# firealarm.net
KiCad netlist of a schematic drawn in EAGLE
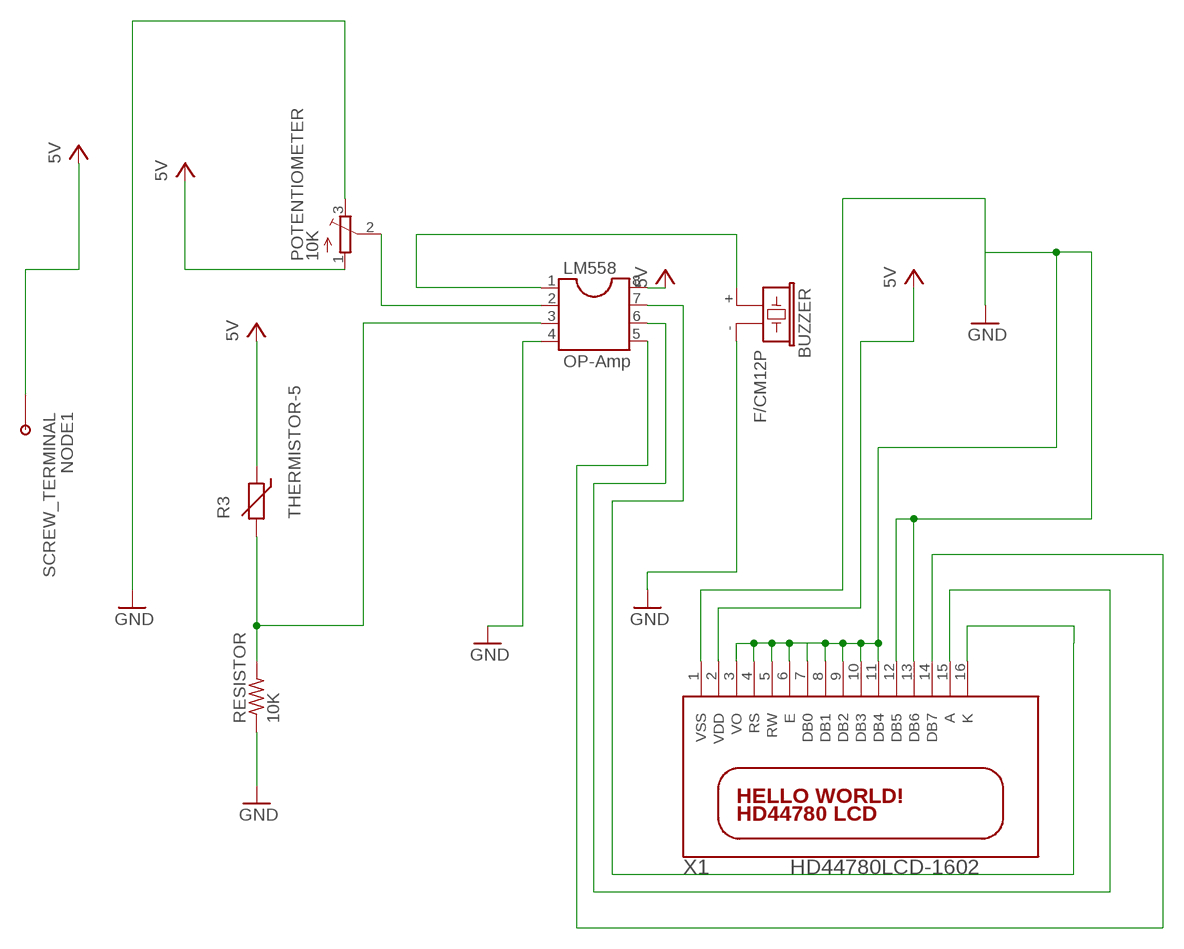
[diagram p0: schematic, sheet 1]

(export (version "E")
  (design (tool "Eeschema 10.0.6"))
  (components
    (comp (ref "BUZZER")
      (value "F/CM12P")
      (footprint "eagle-import:F_CM12P")
      (libsource (lib "eagle-import") (part "F/CM12P"))
    )
    (comp (ref "LM558")
      (value "OP-Amp")
      (footprint "eagle-import:SOCKET-08")
      (libsource (lib "eagle-import") (part "DIL8S"))
    )
    (comp (ref "NODE1")
      (value "SCREW_TERMINAL")
      (footprint "eagle-import:NINIGI_PCB_1M4")
      (libsource (lib "eagle-import") (part "PCB_SCREW_TERMINAL"))
    )
    (comp (ref "POTENTIOMETER")
      (value "10K")
      (footprint "eagle-import:3223G")
      (libsource (lib "eagle-import") (part "TRIM_EU-3223G"))
    )
    (comp (ref "R3")
      (value "THERMISTOR-5")
      (footprint "eagle-import:R-5")
      (libsource (lib "eagle-import") (part "THERMISTOR-5"))
    )
    (comp (ref "RESISTOR")
      (value "10K")
      (footprint "eagle-import:0204V")
      (libsource (lib "eagle-import") (part "R-US_0204/2V"))
    )
    (comp (ref "X1")
      (value "HD44780LCD-1602")
      (footprint "eagle-import:LCD1602")
      (libsource (lib "eagle-import") (part "HD44780LCD-1602"))
    )
  )
  (nets
    (net (code "1") (name "5V") (class "Default")
      (node (ref "LM558") (pin "8") (pinfunction "8_8") (pintype "passive"))
      (node (ref "NODE1") (pin "1") (pinfunction "P$1_1") (pintype "bidirectional"))
      (node (ref "NODE1") (pin "2") (pinfunction "P$1_2") (pintype "bidirectional"))
      (node (ref "NODE1") (pin "3") (pinfunction "P$1_3") (pintype "bidirectional"))
      (node (ref "NODE1") (pin "4") (pinfunction "P$1_4") (pintype "bidirectional"))
      (node (ref "NODE1") (pin "C") (pinfunction "P$1_C") (pintype "bidirectional"))
      (node (ref "POTENTIOMETER") (pin "1") (pinfunction "A_1") (pintype "passive"))
      (node (ref "R3") (pin "1") (pinfunction "1_1") (pintype "passive"))
      (node (ref "X1") (pin "2") (pinfunction "VDD_2") (pintype "power_in"))
    )
    (net (code "2") (name "GND") (class "Default")
      (node (ref "BUZZER") (pin "-") (pinfunction "2_-") (pintype "passive"))
      (node (ref "LM558") (pin "4") (pinfunction "4_4") (pintype "passive"))
      (node (ref "POTENTIOMETER") (pin "3") (pinfunction "E_3") (pintype "passive"))
      (node (ref "RESISTOR") (pin "1") (pinfunction "1_1") (pintype "passive"))
      (node (ref "X1") (pin "1") (pinfunction "VSS_1") (pintype "power_in"))
      (node (ref "X1") (pin "10") (pinfunction "DB3_10") (pintype "bidirectional"))
      (node (ref "X1") (pin "11") (pinfunction "DB4_11") (pintype "bidirectional"))
      (node (ref "X1") (pin "12") (pinfunction "DB5_12") (pintype "bidirectional"))
      (node (ref "X1") (pin "13") (pinfunction "DB6_13") (pintype "bidirectional"))
      (node (ref "X1") (pin "3") (pinfunction "VO_3") (pintype "input"))
      (node (ref "X1") (pin "4") (pinfunction "RS_4") (pintype "input"))
      (node (ref "X1") (pin "5") (pinfunction "RW_5") (pintype "input"))
      (node (ref "X1") (pin "6") (pinfunction "E_6") (pintype "input"))
      (node (ref "X1") (pin "8") (pinfunction "DB1_8") (pintype "bidirectional"))
      (node (ref "X1") (pin "9") (pinfunction "DB2_9") (pintype "bidirectional"))
    )
    (net (code "3") (name "Net-(BUZZER-1)") (class "Default")
      (node (ref "BUZZER") (pin "+") (pinfunction "1_+") (pintype "passive"))
      (node (ref "LM558") (pin "1") (pinfunction "1_1") (pintype "passive"))
    )
    (net (code "4") (name "Net-(LM558-Pad3)") (class "Default")
      (node (ref "LM558") (pin "3") (pinfunction "3_3") (pintype "passive"))
      (node (ref "R3") (pin "2") (pinfunction "2_2") (pintype "passive"))
      (node (ref "RESISTOR") (pin "2") (pinfunction "2_2") (pintype "passive"))
    )
    (net (code "5") (name "Net-(POTENTIOMETER-S)") (class "Default")
      (node (ref "LM558") (pin "2") (pinfunction "2_2") (pintype "passive"))
      (node (ref "POTENTIOMETER") (pin "2") (pinfunction "S_2") (pintype "passive"))
    )
    (net (code "6") (name "Net-(X1-A)") (class "Default")
      (node (ref "LM558") (pin "6") (pinfunction "6_6") (pintype "passive"))
      (node (ref "X1") (pin "15") (pinfunction "A_15") (pintype "input"))
    )
    (net (code "7") (name "Net-(X1-DB7)") (class "Default")
      (node (ref "LM558") (pin "5") (pinfunction "5_5") (pintype "passive"))
      (node (ref "X1") (pin "14") (pinfunction "DB7_14") (pintype "bidirectional"))
    )
    (net (code "8") (name "Net-(X1-K)") (class "Default")
      (node (ref "LM558") (pin "7") (pinfunction "7_7") (pintype "passive"))
      (node (ref "X1") (pin "16") (pinfunction "K_16") (pintype "input"))
    )
    (net (code "9") (name "unconnected-(X1-DB0-Pad7)") (class "Default")
      (node (ref "X1") (pin "7") (pinfunction "DB0_7") (pintype "bidirectional"))
    )
  )
)
